# LB_BIT_i6_DIMMER-v02_rev1.net
KiCad netlist of a schematic drawn in EAGLE
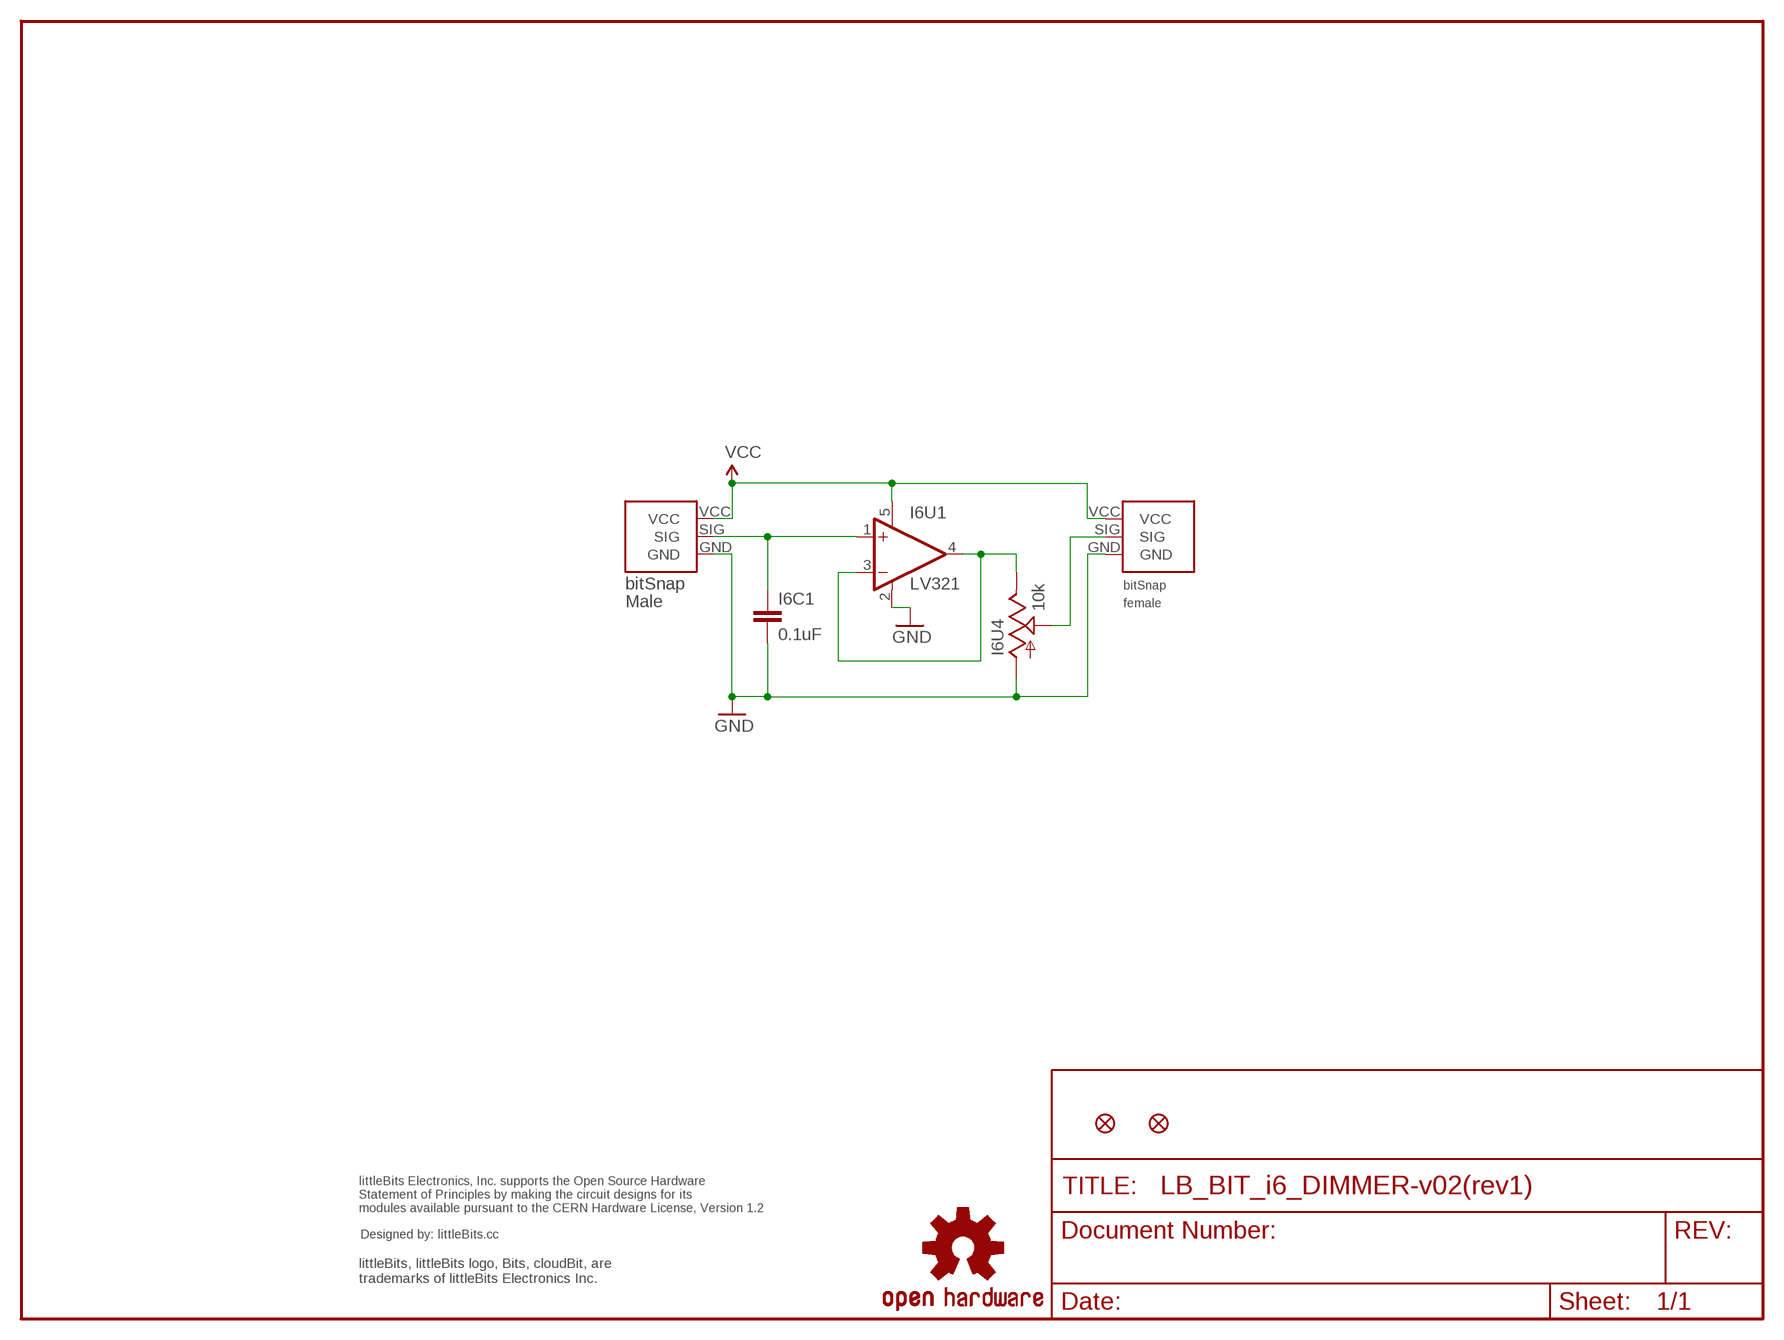
[diagram p0: schematic, sheet 1]

(export (version "E")
  (design (tool "Eeschema 10.0.6"))
  (components
    (comp (ref "I6BSF")
      (value "BITSNAP_FEMALE")
      (footprint "eagle-import:BITSNAP_FEMALE")
      (libsource (lib "eagle-import") (part "BITSNAP_FEMALE"))
    )
    (comp (ref "I6BSM")
      (value "BITSNAP_MALE")
      (footprint "eagle-import:BITSNAP_MALE")
      (libsource (lib "eagle-import") (part "BITSNAP_MALE"))
    )
    (comp (ref "I6C1")
      (value "0.1uF")
      (footprint "eagle-import:0603-CAP")
      (libsource (lib "eagle-import") (part "CAP0603-CAP"))
    )
    (comp (ref "I6U1")
      (value "LV321")
      (footprint "eagle-import:SC70-5")
      (libsource (lib "eagle-import") (part "LV321"))
    )
    (comp (ref "I6U4")
      (value "10k")
      (footprint "eagle-import:ALPS_POT")
      (libsource (lib "eagle-import") (part "POT"))
    )
    (comp (ref "JP1")
      (value "FIDUCIAL1X2.5")
      (footprint "eagle-import:FIDUCIAL-1X2.5")
      (libsource (lib "eagle-import") (part "FIDUCIAL1X2.5"))
    )
    (comp (ref "JP2")
      (value "FIDUCIAL1X2.5")
      (footprint "eagle-import:FIDUCIAL-1X2.5")
      (libsource (lib "eagle-import") (part "FIDUCIAL1X2.5"))
    )
    (comp (ref "U$1")
      (value "OSHWCREDIT")
      (footprint "eagle-import:OSHWCREDIT")
      (libsource (lib "eagle-import") (part "OSHWCREDIT"))
    )
    (comp (ref "U$3")
      (value "OSHW-LOGOL")
      (footprint "eagle-import:OSHW-LOGO-L")
      (libsource (lib "eagle-import") (part "OSHW-LOGOL"))
    )
  )
  (nets
    (net (code "1") (name "GND") (class "Default")
      (node (ref "I6BSF") (pin "GND") (pinfunction "GND_GND") (pintype "bidirectional"))
      (node (ref "I6BSM") (pin "GND") (pinfunction "GND_GND") (pintype "bidirectional"))
      (node (ref "I6C1") (pin "2") (pinfunction "2_2") (pintype "passive"))
      (node (ref "I6U1") (pin "2") (pinfunction "V-_2") (pintype "power_in"))
      (node (ref "I6U4") (pin "P$3") (pinfunction "A_P$3") (pintype "passive"))
    )
    (net (code "2") (name "Net-(I6U1-+IN)") (class "Default")
      (node (ref "I6BSM") (pin "SIG") (pinfunction "SIG_SIG") (pintype "bidirectional"))
      (node (ref "I6C1") (pin "1") (pinfunction "1_1") (pintype "passive"))
      (node (ref "I6U1") (pin "1") (pinfunction "+IN_1") (pintype "input"))
    )
    (net (code "3") (name "Net-(I6U1--IN)") (class "Default")
      (node (ref "I6U1") (pin "3") (pinfunction "-IN_3") (pintype "input"))
      (node (ref "I6U1") (pin "4") (pinfunction "OUT_4") (pintype "output"))
      (node (ref "I6U4") (pin "P$1") (pinfunction "E_P$1") (pintype "passive"))
    )
    (net (code "4") (name "Net-(I6U4-S)") (class "Default")
      (node (ref "I6BSF") (pin "SIG") (pinfunction "SIG_SIG") (pintype "bidirectional"))
      (node (ref "I6U4") (pin "P$2") (pinfunction "S_P$2") (pintype "passive"))
    )
    (net (code "5") (name "VCC") (class "Default")
      (node (ref "I6BSF") (pin "VCC") (pinfunction "VCC_VCC") (pintype "bidirectional"))
      (node (ref "I6BSM") (pin "VCC") (pinfunction "VCC_VCC") (pintype "bidirectional"))
      (node (ref "I6U1") (pin "5") (pinfunction "V+_5") (pintype "power_in"))
    )
  )
)
